# design.net
KiCad netlist of a schematic drawn in EasyEDA
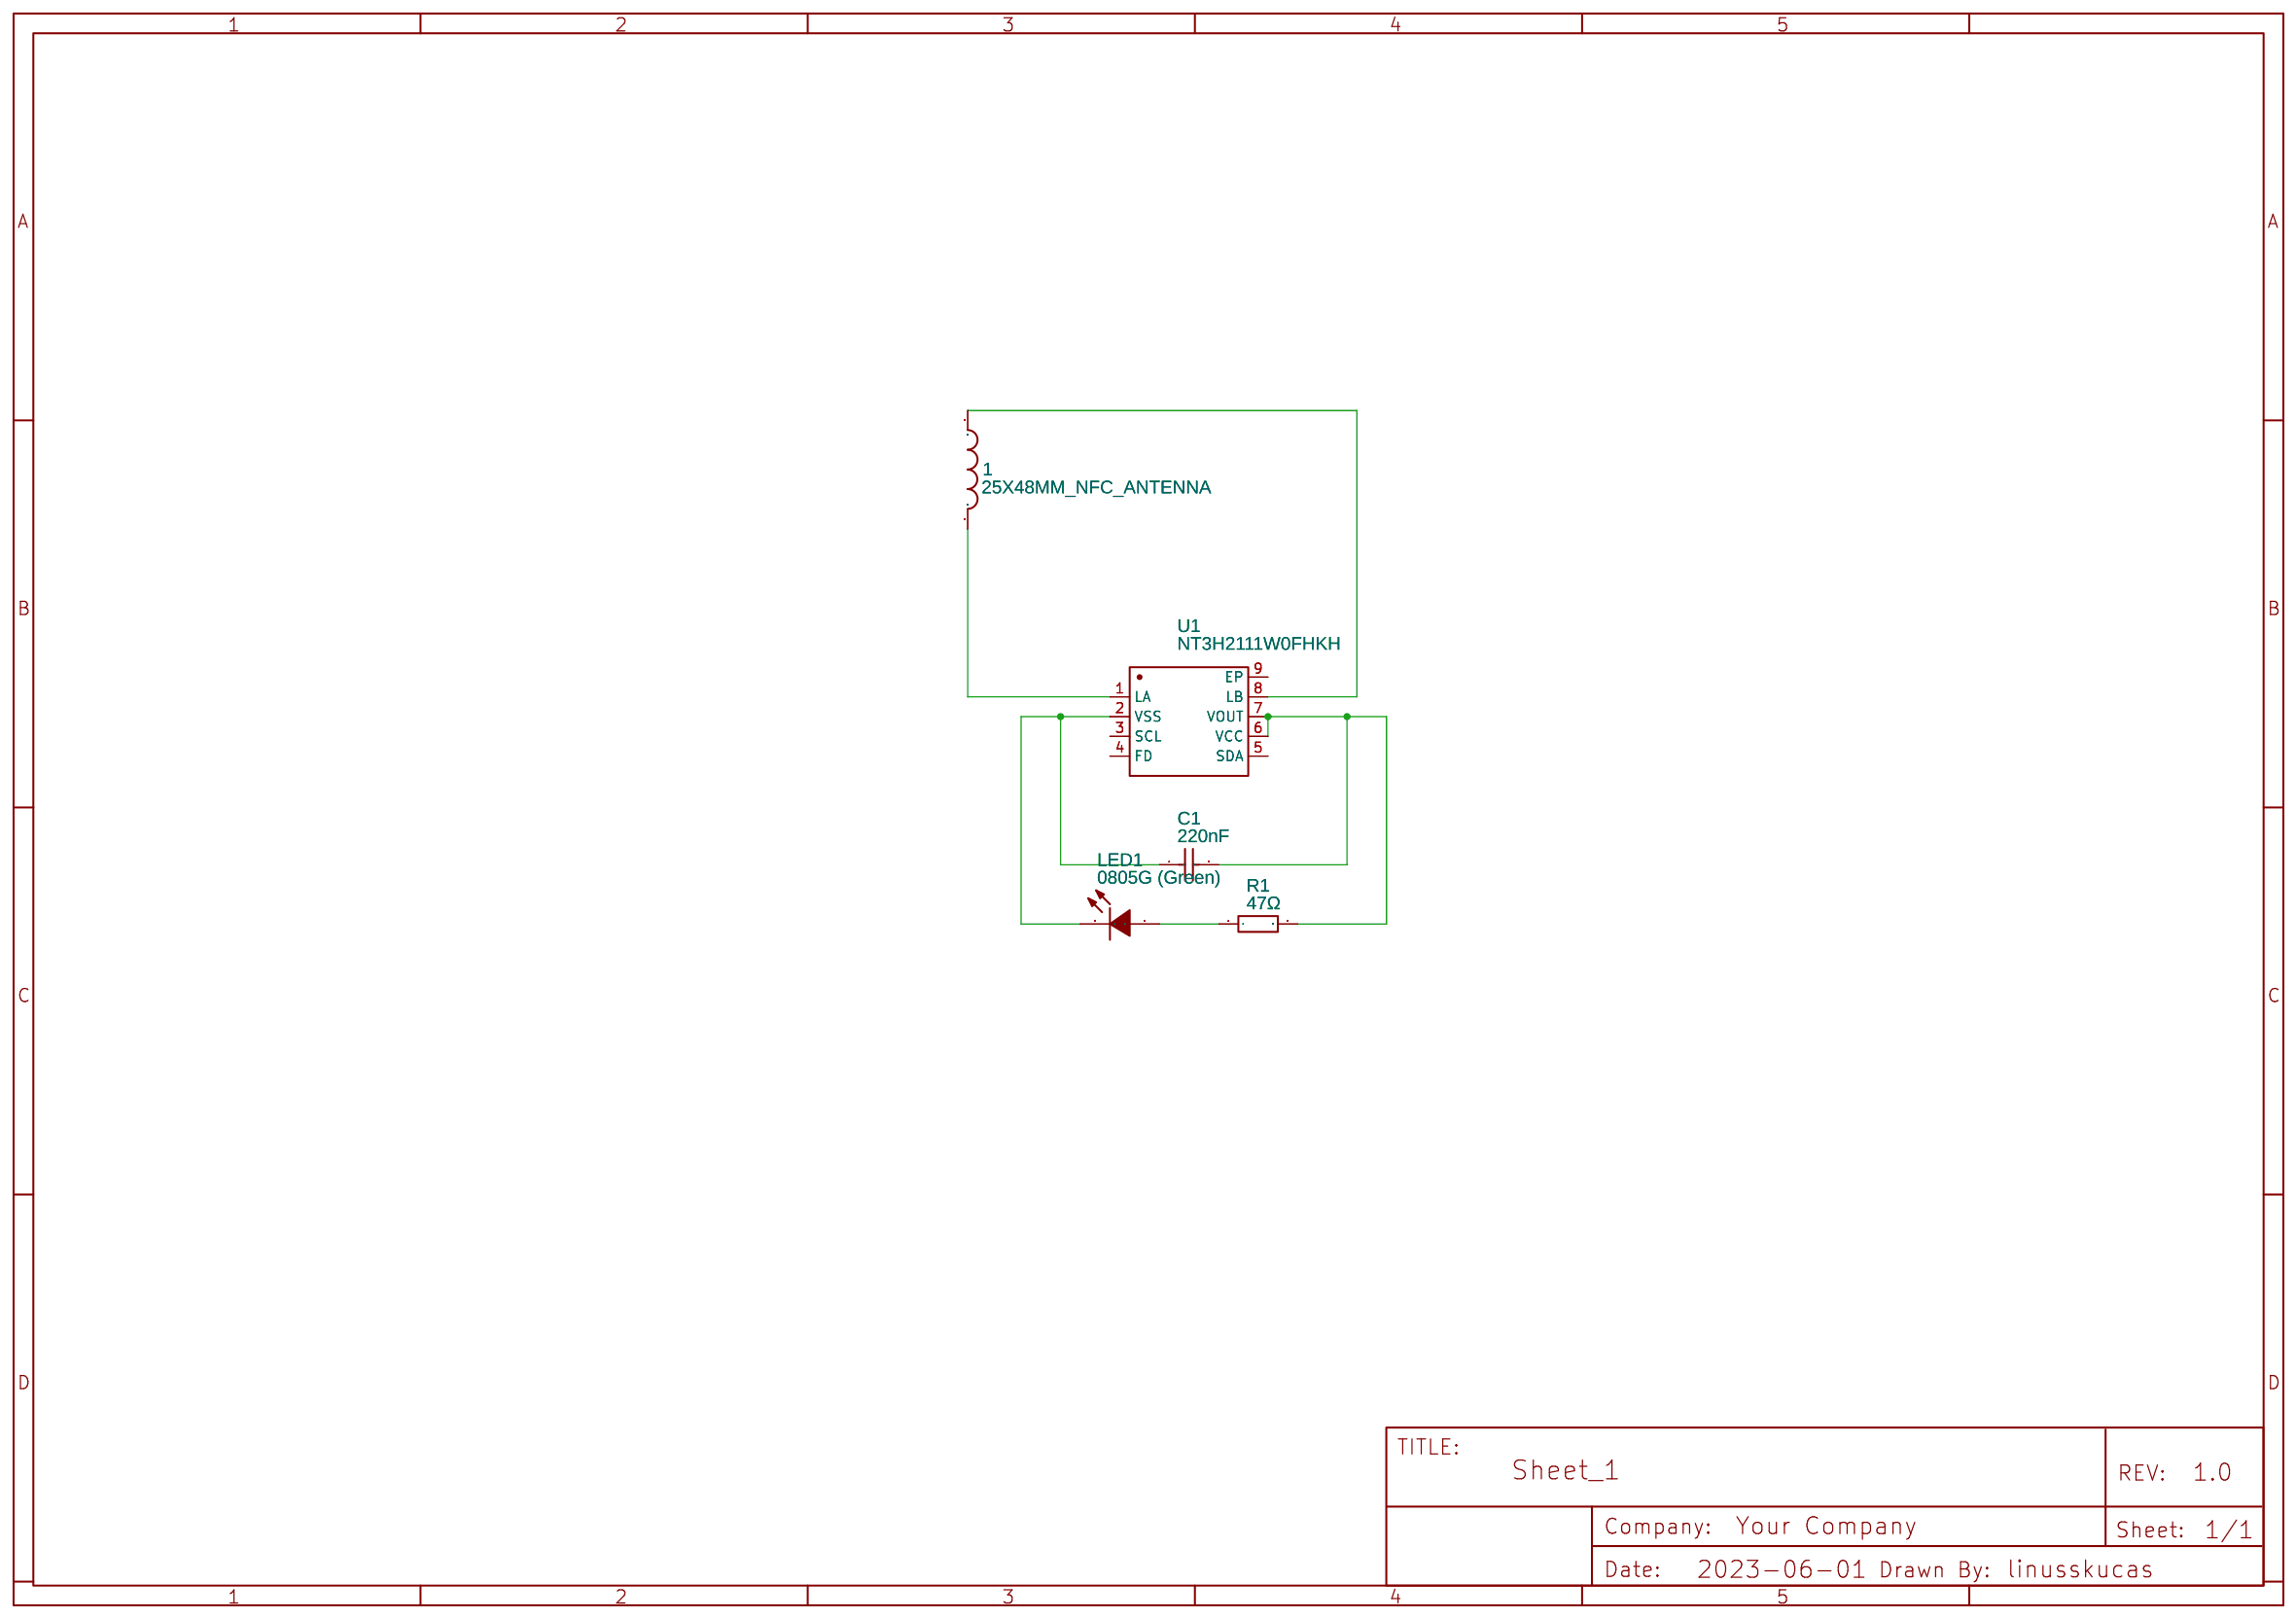
[diagram p0: schematic sheet]

(export (version "E")
  (design (tool "Eeschema 10.0.6"))
  (components
    (comp (ref "1") (value "25X48MM_NFC_ANTENNA") (libsource (lib "") (part "25X48MM_NFC_ANTENNA")))
    (comp (ref "C1")
      (value "220nF")
      (fields
        (field (name "BOM_Manufacturer Part") "CL10B224KA8NNNC")
        (field (name "BOM_Supplier Part") "C21120")
      )
      (libsource (lib "") (part "CL10B224KA8NNNC"))
    )
    (comp (ref "LED1")
      (value "0805G (Green)")
      (fields (field (name "BOM_Manufacturer Part") "KT-0805翠绿") (field (name "BOM_Supplier Part") "C2297"))
      (libsource (lib "") (part "0805G (Green)"))
    )
    (comp (ref "R1")
      (value "47Ω")
      (fields
        (field (name "BOM_Manufacturer Part") "0603WAF470JT5E")
        (field (name "BOM_Supplier Part") "C23182")
      )
      (libsource (lib "") (part "0603WAF470JT5E"))
    )
    (comp (ref "U1")
      (value "NT3H2111W0FHKH")
      (fields (field (name "BOM_Supplier Part") "C710403"))
      (libsource (lib "") (part "NT3H2111W0FHKH"))
    )
  )
  (nets
    (net (code "1") (name "Net-(LED1-A)") (class "Default")
      (node (ref "LED1") (pin "1") (pinfunction "A_1") (pintype "unspecified"))
      (node (ref "R1") (pin "1") (pinfunction "1_1") (pintype "input"))
    )
    (net (code "2") (name "Net-(LED1-K)") (class "Default")
      (node (ref "C1") (pin "1") (pinfunction "1_1") (pintype "input"))
      (node (ref "LED1") (pin "2") (pinfunction "K_2") (pintype "unspecified"))
      (node (ref "U1") (pin "2") (pinfunction "VSS_2") (pintype "unspecified"))
    )
    (net (code "3") (name "Net-(U1-LA)") (class "Default")
      (node (ref "1") (pin "P$2") (pinfunction "P$2_P$2") (pintype "bidirectional"))
      (node (ref "U1") (pin "1") (pinfunction "LA_1") (pintype "unspecified"))
    )
    (net (code "4") (name "Net-(U1-LB)") (class "Default")
      (node (ref "1") (pin "P$1") (pinfunction "P$1_P$1") (pintype "bidirectional"))
      (node (ref "U1") (pin "8") (pinfunction "LB_8") (pintype "unspecified"))
    )
    (net (code "5") (name "Net-(U1-VCC)") (class "Default")
      (node (ref "C1") (pin "2") (pinfunction "2_2") (pintype "input"))
      (node (ref "R1") (pin "2") (pinfunction "2_2") (pintype "input"))
      (node (ref "U1") (pin "6") (pinfunction "VCC_6") (pintype "unspecified"))
      (node (ref "U1") (pin "7") (pinfunction "VOUT_7") (pintype "unspecified"))
    )
    (net (code "6") (name "unconnected-(U1-EP-Pad9)") (class "Default")
      (node (ref "U1") (pin "9") (pinfunction "EP_9") (pintype "unspecified"))
    )
    (net (code "7") (name "unconnected-(U1-FD-Pad4)") (class "Default")
      (node (ref "U1") (pin "4") (pinfunction "FD_4") (pintype "unspecified"))
    )
    (net (code "8") (name "unconnected-(U1-SCL-Pad3)") (class "Default")
      (node (ref "U1") (pin "3") (pinfunction "SCL_3") (pintype "unspecified"))
    )
    (net (code "9") (name "unconnected-(U1-SDA-Pad5)") (class "Default")
      (node (ref "U1") (pin "5") (pinfunction "SDA_5") (pintype "unspecified"))
    )
  )
)
